# SCH_LEFT_2025-11-04.net
KiCad netlist of a schematic drawn in EasyEDA
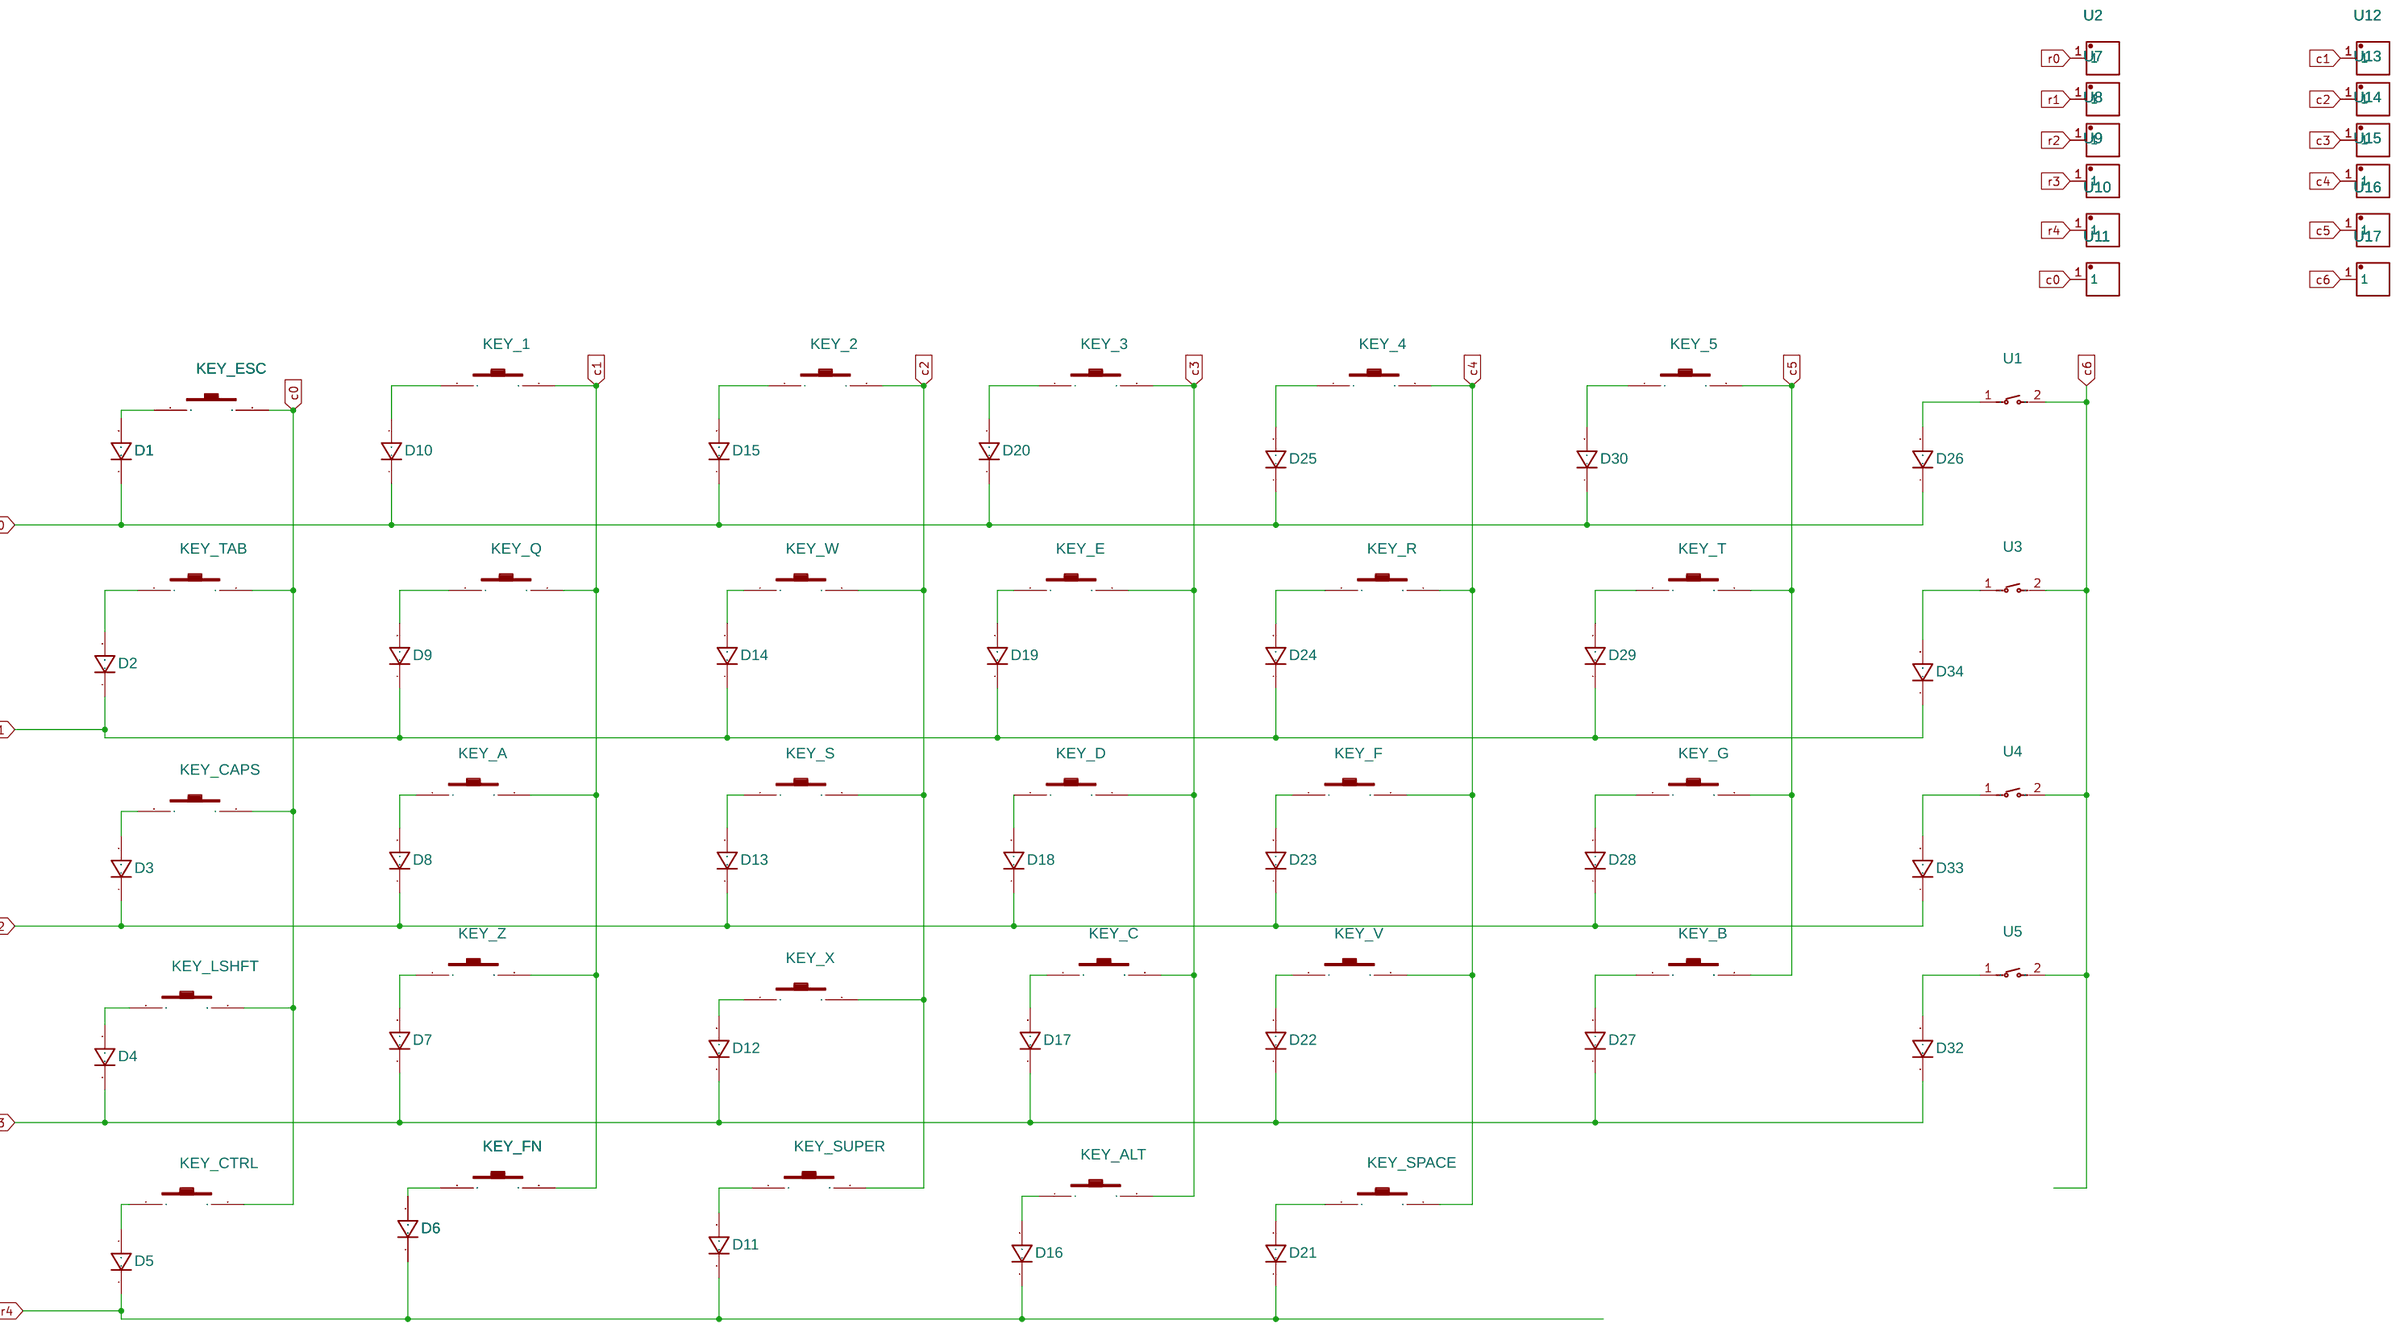
[diagram p0: schematic sheet]

(export (version "E")
  (design (tool "Eeschema 10.0.6"))
  (components
    (comp (ref "D1")
      (value "1N4148W")
      (fields (field (name "Manufacturer") "SMC Diode Solutions"))
      (libsource (lib "") (part "1N4148W"))
    )
    (comp (ref "D2")
      (value "1N4148W")
      (fields (field (name "Manufacturer") "SMC Diode Solutions"))
      (libsource (lib "") (part "1N4148W"))
    )
    (comp (ref "D3")
      (value "1N4148W")
      (fields (field (name "Manufacturer") "SMC Diode Solutions"))
      (libsource (lib "") (part "1N4148W"))
    )
    (comp (ref "D4")
      (value "1N4148W")
      (fields (field (name "Manufacturer") "SMC Diode Solutions"))
      (libsource (lib "") (part "1N4148W"))
    )
    (comp (ref "D5")
      (value "1N4148W")
      (fields (field (name "Manufacturer") "SMC Diode Solutions"))
      (libsource (lib "") (part "1N4148W"))
    )
    (comp (ref "D6")
      (value "1N4148W")
      (fields (field (name "Manufacturer") "SMC Diode Solutions"))
      (libsource (lib "") (part "1N4148W"))
    )
    (comp (ref "D7")
      (value "1N4148W")
      (fields (field (name "Manufacturer") "SMC Diode Solutions"))
      (libsource (lib "") (part "1N4148W"))
    )
    (comp (ref "D8")
      (value "1N4148W")
      (fields (field (name "Manufacturer") "SMC Diode Solutions"))
      (libsource (lib "") (part "1N4148W"))
    )
    (comp (ref "D9")
      (value "1N4148W")
      (fields (field (name "Manufacturer") "SMC Diode Solutions"))
      (libsource (lib "") (part "1N4148W"))
    )
    (comp (ref "D10")
      (value "1N4148W")
      (fields (field (name "Manufacturer") "SMC Diode Solutions"))
      (libsource (lib "") (part "1N4148W"))
    )
    (comp (ref "D11")
      (value "1N4148W")
      (fields (field (name "Manufacturer") "SMC Diode Solutions"))
      (libsource (lib "") (part "1N4148W"))
    )
    (comp (ref "D12")
      (value "1N4148W")
      (fields (field (name "Manufacturer") "SMC Diode Solutions"))
      (libsource (lib "") (part "1N4148W"))
    )
    (comp (ref "D13")
      (value "1N4148W")
      (fields (field (name "Manufacturer") "SMC Diode Solutions"))
      (libsource (lib "") (part "1N4148W"))
    )
    (comp (ref "D14")
      (value "1N4148W")
      (fields (field (name "Manufacturer") "SMC Diode Solutions"))
      (libsource (lib "") (part "1N4148W"))
    )
    (comp (ref "D15")
      (value "1N4148W")
      (fields (field (name "Manufacturer") "SMC Diode Solutions"))
      (libsource (lib "") (part "1N4148W"))
    )
    (comp (ref "D16")
      (value "1N4148W")
      (fields (field (name "Manufacturer") "SMC Diode Solutions"))
      (libsource (lib "") (part "1N4148W"))
    )
    (comp (ref "D17")
      (value "1N4148W")
      (fields (field (name "Manufacturer") "SMC Diode Solutions"))
      (libsource (lib "") (part "1N4148W"))
    )
    (comp (ref "D18")
      (value "1N4148W")
      (fields (field (name "Manufacturer") "SMC Diode Solutions"))
      (libsource (lib "") (part "1N4148W"))
    )
    (comp (ref "D19")
      (value "1N4148W")
      (fields (field (name "Manufacturer") "SMC Diode Solutions"))
      (libsource (lib "") (part "1N4148W"))
    )
    (comp (ref "D20")
      (value "1N4148W")
      (fields (field (name "Manufacturer") "SMC Diode Solutions"))
      (libsource (lib "") (part "1N4148W"))
    )
    (comp (ref "D21")
      (value "1N4148W")
      (fields (field (name "Manufacturer") "SMC Diode Solutions"))
      (libsource (lib "") (part "1N4148W"))
    )
    (comp (ref "D22")
      (value "1N4148W")
      (fields (field (name "Manufacturer") "SMC Diode Solutions"))
      (libsource (lib "") (part "1N4148W"))
    )
    (comp (ref "D23")
      (value "1N4148W")
      (fields (field (name "Manufacturer") "SMC Diode Solutions"))
      (libsource (lib "") (part "1N4148W"))
    )
    (comp (ref "D24")
      (value "1N4148W")
      (fields (field (name "Manufacturer") "SMC Diode Solutions"))
      (libsource (lib "") (part "1N4148W"))
    )
    (comp (ref "D25")
      (value "1N4148W")
      (fields (field (name "Manufacturer") "SMC Diode Solutions"))
      (libsource (lib "") (part "1N4148W"))
    )
    (comp (ref "D26")
      (value "1N4148W")
      (fields (field (name "Manufacturer") "SMC Diode Solutions"))
      (libsource (lib "") (part "1N4148W"))
    )
    (comp (ref "D27")
      (value "1N4148W")
      (fields (field (name "Manufacturer") "SMC Diode Solutions"))
      (libsource (lib "") (part "1N4148W"))
    )
    (comp (ref "D28")
      (value "1N4148W")
      (fields (field (name "Manufacturer") "SMC Diode Solutions"))
      (libsource (lib "") (part "1N4148W"))
    )
    (comp (ref "D29")
      (value "1N4148W")
      (fields (field (name "Manufacturer") "SMC Diode Solutions"))
      (libsource (lib "") (part "1N4148W"))
    )
    (comp (ref "D30")
      (value "1N4148W")
      (fields (field (name "Manufacturer") "SMC Diode Solutions"))
      (libsource (lib "") (part "1N4148W"))
    )
    (comp (ref "D32")
      (value "1N4148W")
      (fields (field (name "Manufacturer") "SMC Diode Solutions"))
      (libsource (lib "") (part "1N4148W"))
    )
    (comp (ref "D33")
      (value "1N4148W")
      (fields (field (name "Manufacturer") "SMC Diode Solutions"))
      (libsource (lib "") (part "1N4148W"))
    )
    (comp (ref "D34")
      (value "1N4148W")
      (fields (field (name "Manufacturer") "SMC Diode Solutions"))
      (libsource (lib "") (part "1N4148W"))
    )
    (comp (ref "KEY_1") (value "Outemu Switch") (libsource (lib "") (part "Outemu Switch_14")))
    (comp (ref "KEY_2") (value "Outemu Switch") (libsource (lib "") (part "Outemu Switch_14")))
    (comp (ref "KEY_3") (value "Outemu Switch") (libsource (lib "") (part "Outemu Switch_14")))
    (comp (ref "KEY_4") (value "Outemu Switch") (libsource (lib "") (part "Outemu Switch_14")))
    (comp (ref "KEY_5") (value "Outemu Switch") (libsource (lib "") (part "Outemu Switch_14")))
    (comp (ref "KEY_A") (value "Outemu Switch") (libsource (lib "") (part "Outemu Switch_1")))
    (comp (ref "KEY_ALT") (value "Outemu Switch") (libsource (lib "") (part "Outemu Switch_13")))
    (comp (ref "KEY_B") (value "Outemu Switch") (libsource (lib "") (part "Outemu Switch_8")))
    (comp (ref "KEY_C") (value "Outemu Switch") (libsource (lib "") (part "Outemu Switch_16")))
    (comp (ref "KEY_CAPS") (value "Outemu Switch") (libsource (lib "") (part "Outemu Switch_10")))
    (comp (ref "KEY_CTRL") (value "Outemu Switch") (libsource (lib "") (part "Outemu Switch_17")))
    (comp (ref "KEY_D") (value "Outemu Switch") (libsource (lib "") (part "Outemu Switch_12")))
    (comp (ref "KEY_E") (value "Outemu Switch") (libsource (lib "") (part "Outemu Switch_3")))
    (comp (ref "KEY_ESC") (value "Outemu Switch") (libsource (lib "") (part "Outemu Switch")))
    (comp (ref "KEY_F") (value "Outemu Switch") (libsource (lib "") (part "Outemu Switch_18")))
    (comp (ref "KEY_FN") (value "Outemu Switch") (libsource (lib "") (part "Outemu Switch_11")))
    (comp (ref "KEY_G") (value "Outemu Switch") (libsource (lib "") (part "Outemu Switch_20")))
    (comp (ref "KEY_LSHFT") (value "Outemu Switch") (libsource (lib "") (part "Outemu Switch_22")))
    (comp (ref "KEY_Q") (value "Outemu Switch") (libsource (lib "") (part "Outemu Switch_2")))
    (comp (ref "KEY_R") (value "Outemu Switch") (libsource (lib "") (part "Outemu Switch_24")))
    (comp (ref "KEY_S") (value "Outemu Switch") (libsource (lib "") (part "Outemu Switch_9")))
    (comp (ref "KEY_SPACE") (value "Outemu Switch") (libsource (lib "") (part "Outemu Switch_19")))
    (comp (ref "KEY_SUPER") (value "Outemu Switch") (libsource (lib "") (part "Outemu Switch_7")))
    (comp (ref "KEY_T") (value "Outemu Switch") (libsource (lib "") (part "Outemu Switch_21")))
    (comp (ref "KEY_TAB") (value "Outemu Switch") (libsource (lib "") (part "Outemu Switch_15")))
    (comp (ref "KEY_V") (value "Outemu Switch") (libsource (lib "") (part "Outemu Switch_6")))
    (comp (ref "KEY_W") (value "Outemu Switch") (libsource (lib "") (part "Outemu Switch_4")))
    (comp (ref "KEY_X") (value "Outemu Switch") (libsource (lib "") (part "Outemu Switch_5")))
    (comp (ref "KEY_Z") (value "Outemu Switch") (libsource (lib "") (part "Outemu Switch_23")))
    (comp (ref "U1")
      (value "ZX-QC34-2TPDZ")
      (fields (field (name "Manufacturer") "Megastar(兆星)"))
      (libsource (lib "") (part "ZX-QC34-2TPDZ"))
    )
    (comp (ref "U2")
      (value "54102-T06-00")
      (fields (field (name "Manufacturer") "Amphenol"))
      (libsource (lib "") (part "54102-T06-00"))
    )
    (comp (ref "U3")
      (value "ZX-QC34-2TPDZ")
      (fields (field (name "Manufacturer") "Megastar(兆星)"))
      (libsource (lib "") (part "ZX-QC34-2TPDZ"))
    )
    (comp (ref "U4")
      (value "ZX-QC34-2TPDZ")
      (fields (field (name "Manufacturer") "Megastar(兆星)"))
      (libsource (lib "") (part "ZX-QC34-2TPDZ"))
    )
    (comp (ref "U5")
      (value "ZX-QC34-2TPDZ")
      (fields (field (name "Manufacturer") "Megastar(兆星)"))
      (libsource (lib "") (part "ZX-QC34-2TPDZ"))
    )
    (comp (ref "U7")
      (value "54102-T06-00")
      (fields (field (name "Manufacturer") "Amphenol"))
      (libsource (lib "") (part "54102-T06-00"))
    )
    (comp (ref "U8")
      (value "54102-T06-00")
      (fields (field (name "Manufacturer") "Amphenol"))
      (libsource (lib "") (part "54102-T06-00"))
    )
    (comp (ref "U9")
      (value "54102-T06-00")
      (fields (field (name "Manufacturer") "Amphenol"))
      (libsource (lib "") (part "54102-T06-00"))
    )
    (comp (ref "U10")
      (value "54102-T06-00")
      (fields (field (name "Manufacturer") "Amphenol"))
      (libsource (lib "") (part "54102-T06-00"))
    )
    (comp (ref "U11")
      (value "54102-T06-00")
      (fields (field (name "Manufacturer") "Amphenol"))
      (libsource (lib "") (part "54102-T06-00"))
    )
    (comp (ref "U12")
      (value "54102-T06-00")
      (fields (field (name "Manufacturer") "Amphenol"))
      (libsource (lib "") (part "54102-T06-00"))
    )
    (comp (ref "U13")
      (value "54102-T06-00")
      (fields (field (name "Manufacturer") "Amphenol"))
      (libsource (lib "") (part "54102-T06-00"))
    )
    (comp (ref "U14")
      (value "54102-T06-00")
      (fields (field (name "Manufacturer") "Amphenol"))
      (libsource (lib "") (part "54102-T06-00"))
    )
    (comp (ref "U15")
      (value "54102-T06-00")
      (fields (field (name "Manufacturer") "Amphenol"))
      (libsource (lib "") (part "54102-T06-00"))
    )
    (comp (ref "U16")
      (value "54102-T06-00")
      (fields (field (name "Manufacturer") "Amphenol"))
      (libsource (lib "") (part "54102-T06-00"))
    )
    (comp (ref "U17")
      (value "54102-T06-00")
      (fields (field (name "Manufacturer") "Amphenol"))
      (libsource (lib "") (part "54102-T06-00"))
    )
  )
  (nets
    (net (code "1") (name "Net-(D1-Pad2)") (class "Default")
      (node (ref "D1") (pin "2") (pinfunction "2_2") (pintype "unspecified"))
      (node (ref "KEY_ESC") (pin "1") (pinfunction "1_1") (pintype "input"))
    )
    (net (code "2") (name "Net-(D2-Pad2)") (class "Default")
      (node (ref "D2") (pin "2") (pinfunction "2_2") (pintype "unspecified"))
      (node (ref "KEY_TAB") (pin "1") (pinfunction "1_1") (pintype "input"))
    )
    (net (code "3") (name "Net-(D3-Pad2)") (class "Default")
      (node (ref "D3") (pin "2") (pinfunction "2_2") (pintype "unspecified"))
      (node (ref "KEY_CAPS") (pin "1") (pinfunction "1_1") (pintype "input"))
    )
    (net (code "4") (name "Net-(D4-Pad2)") (class "Default")
      (node (ref "D4") (pin "2") (pinfunction "2_2") (pintype "unspecified"))
      (node (ref "KEY_LSHFT") (pin "1") (pinfunction "1_1") (pintype "input"))
    )
    (net (code "5") (name "Net-(D5-Pad2)") (class "Default")
      (node (ref "D5") (pin "2") (pinfunction "2_2") (pintype "unspecified"))
      (node (ref "KEY_CTRL") (pin "1") (pinfunction "1_1") (pintype "input"))
    )
    (net (code "6") (name "Net-(D6-Pad2)") (class "Default")
      (node (ref "D6") (pin "2") (pinfunction "2_2") (pintype "unspecified"))
      (node (ref "KEY_FN") (pin "1") (pinfunction "1_1") (pintype "input"))
    )
    (net (code "7") (name "Net-(D7-Pad2)") (class "Default")
      (node (ref "D7") (pin "2") (pinfunction "2_2") (pintype "unspecified"))
      (node (ref "KEY_Z") (pin "1") (pinfunction "1_1") (pintype "input"))
    )
    (net (code "8") (name "Net-(D8-Pad2)") (class "Default")
      (node (ref "D8") (pin "2") (pinfunction "2_2") (pintype "unspecified"))
      (node (ref "KEY_A") (pin "1") (pinfunction "1_1") (pintype "input"))
    )
    (net (code "9") (name "Net-(D9-Pad2)") (class "Default")
      (node (ref "D9") (pin "2") (pinfunction "2_2") (pintype "unspecified"))
      (node (ref "KEY_Q") (pin "1") (pinfunction "1_1") (pintype "input"))
    )
    (net (code "10") (name "Net-(D10-Pad2)") (class "Default")
      (node (ref "D10") (pin "2") (pinfunction "2_2") (pintype "unspecified"))
      (node (ref "KEY_1") (pin "1") (pinfunction "1_1") (pintype "input"))
    )
    (net (code "11") (name "Net-(D11-Pad2)") (class "Default")
      (node (ref "D11") (pin "2") (pinfunction "2_2") (pintype "unspecified"))
      (node (ref "KEY_SUPER") (pin "1") (pinfunction "1_1") (pintype "input"))
    )
    (net (code "12") (name "Net-(D12-Pad2)") (class "Default")
      (node (ref "D12") (pin "2") (pinfunction "2_2") (pintype "unspecified"))
      (node (ref "KEY_X") (pin "1") (pinfunction "1_1") (pintype "input"))
    )
    (net (code "13") (name "Net-(D13-Pad2)") (class "Default")
      (node (ref "D13") (pin "2") (pinfunction "2_2") (pintype "unspecified"))
      (node (ref "KEY_S") (pin "1") (pinfunction "1_1") (pintype "input"))
    )
    (net (code "14") (name "Net-(D14-Pad2)") (class "Default")
      (node (ref "D14") (pin "2") (pinfunction "2_2") (pintype "unspecified"))
      (node (ref "KEY_W") (pin "1") (pinfunction "1_1") (pintype "input"))
    )
    (net (code "15") (name "Net-(D15-Pad2)") (class "Default")
      (node (ref "D15") (pin "2") (pinfunction "2_2") (pintype "unspecified"))
      (node (ref "KEY_2") (pin "1") (pinfunction "1_1") (pintype "input"))
    )
    (net (code "16") (name "Net-(D16-Pad2)") (class "Default")
      (node (ref "D16") (pin "2") (pinfunction "2_2") (pintype "unspecified"))
      (node (ref "KEY_ALT") (pin "1") (pinfunction "1_1") (pintype "input"))
    )
    (net (code "17") (name "Net-(D17-Pad2)") (class "Default")
      (node (ref "D17") (pin "2") (pinfunction "2_2") (pintype "unspecified"))
      (node (ref "KEY_C") (pin "1") (pinfunction "1_1") (pintype "input"))
    )
    (net (code "18") (name "Net-(D18-Pad2)") (class "Default")
      (node (ref "D18") (pin "2") (pinfunction "2_2") (pintype "unspecified"))
      (node (ref "KEY_D") (pin "1") (pinfunction "1_1") (pintype "input"))
    )
    (net (code "19") (name "Net-(D19-Pad2)") (class "Default")
      (node (ref "D19") (pin "2") (pinfunction "2_2") (pintype "unspecified"))
      (node (ref "KEY_E") (pin "1") (pinfunction "1_1") (pintype "input"))
    )
    (net (code "20") (name "Net-(D20-Pad2)") (class "Default")
      (node (ref "D20") (pin "2") (pinfunction "2_2") (pintype "unspecified"))
      (node (ref "KEY_3") (pin "1") (pinfunction "1_1") (pintype "input"))
    )
    (net (code "21") (name "Net-(D21-Pad2)") (class "Default")
      (node (ref "D21") (pin "2") (pinfunction "2_2") (pintype "unspecified"))
      (node (ref "KEY_SPACE") (pin "1") (pinfunction "1_1") (pintype "input"))
    )
    (net (code "22") (name "Net-(D22-Pad2)") (class "Default")
      (node (ref "D22") (pin "2") (pinfunction "2_2") (pintype "unspecified"))
      (node (ref "KEY_V") (pin "1") (pinfunction "1_1") (pintype "input"))
    )
    (net (code "23") (name "Net-(D23-Pad2)") (class "Default")
      (node (ref "D23") (pin "2") (pinfunction "2_2") (pintype "unspecified"))
      (node (ref "KEY_F") (pin "1") (pinfunction "1_1") (pintype "input"))
    )
    (net (code "24") (name "Net-(D24-Pad2)") (class "Default")
      (node (ref "D24") (pin "2") (pinfunction "2_2") (pintype "unspecified"))
      (node (ref "KEY_R") (pin "1") (pinfunction "1_1") (pintype "input"))
    )
    (net (code "25") (name "Net-(D25-Pad2)") (class "Default")
      (node (ref "D25") (pin "2") (pinfunction "2_2") (pintype "unspecified"))
      (node (ref "KEY_4") (pin "1") (pinfunction "1_1") (pintype "input"))
    )
    (net (code "26") (name "Net-(D26-Pad2)") (class "Default")
      (node (ref "D26") (pin "2") (pinfunction "2_2") (pintype "unspecified"))
      (node (ref "U1") (pin "1") (pinfunction "1_1") (pintype "unspecified"))
    )
    (net (code "27") (name "Net-(D27-Pad2)") (class "Default")
      (node (ref "D27") (pin "2") (pinfunction "2_2") (pintype "unspecified"))
      (node (ref "KEY_B") (pin "1") (pinfunction "1_1") (pintype "input"))
    )
    (net (code "28") (name "Net-(D28-Pad2)") (class "Default")
      (node (ref "D28") (pin "2") (pinfunction "2_2") (pintype "unspecified"))
      (node (ref "KEY_G") (pin "1") (pinfunction "1_1") (pintype "input"))
    )
    (net (code "29") (name "Net-(D29-Pad2)") (class "Default")
      (node (ref "D29") (pin "2") (pinfunction "2_2") (pintype "unspecified"))
      (node (ref "KEY_T") (pin "1") (pinfunction "1_1") (pintype "input"))
    )
    (net (code "30") (name "Net-(D30-Pad2)") (class "Default")
      (node (ref "D30") (pin "2") (pinfunction "2_2") (pintype "unspecified"))
      (node (ref "KEY_5") (pin "1") (pinfunction "1_1") (pintype "input"))
    )
    (net (code "31") (name "Net-(D32-Pad2)") (class "Default")
      (node (ref "D32") (pin "2") (pinfunction "2_2") (pintype "unspecified"))
      (node (ref "U5") (pin "1") (pinfunction "1_1") (pintype "unspecified"))
    )
    (net (code "32") (name "Net-(D33-Pad2)") (class "Default")
      (node (ref "D33") (pin "2") (pinfunction "2_2") (pintype "unspecified"))
      (node (ref "U4") (pin "1") (pinfunction "1_1") (pintype "unspecified"))
    )
    (net (code "33") (name "Net-(D34-Pad2)") (class "Default")
      (node (ref "D34") (pin "2") (pinfunction "2_2") (pintype "unspecified"))
      (node (ref "U3") (pin "1") (pinfunction "1_1") (pintype "unspecified"))
    )
    (net (code "34") (name "c0") (class "Default")
      (node (ref "KEY_CAPS") (pin "2") (pinfunction "2_2") (pintype "input"))
      (node (ref "KEY_CTRL") (pin "2") (pinfunction "2_2") (pintype "input"))
      (node (ref "KEY_ESC") (pin "2") (pinfunction "2_2") (pintype "input"))
      (node (ref "KEY_LSHFT") (pin "2") (pinfunction "2_2") (pintype "input"))
      (node (ref "KEY_TAB") (pin "2") (pinfunction "2_2") (pintype "input"))
      (node (ref "U11") (pin "1") (pinfunction "1_1") (pintype "unspecified"))
    )
    (net (code "35") (name "c1") (class "Default")
      (node (ref "KEY_1") (pin "2") (pinfunction "2_2") (pintype "input"))
      (node (ref "KEY_A") (pin "2") (pinfunction "2_2") (pintype "input"))
      (node (ref "KEY_FN") (pin "2") (pinfunction "2_2") (pintype "input"))
      (node (ref "KEY_Q") (pin "2") (pinfunction "2_2") (pintype "input"))
      (node (ref "KEY_Z") (pin "2") (pinfunction "2_2") (pintype "input"))
      (node (ref "U12") (pin "1") (pinfunction "1_1") (pintype "unspecified"))
    )
    (net (code "36") (name "c2") (class "Default")
      (node (ref "KEY_2") (pin "2") (pinfunction "2_2") (pintype "input"))
      (node (ref "KEY_S") (pin "2") (pinfunction "2_2") (pintype "input"))
      (node (ref "KEY_SUPER") (pin "2") (pinfunction "2_2") (pintype "input"))
      (node (ref "KEY_W") (pin "2") (pinfunction "2_2") (pintype "input"))
      (node (ref "KEY_X") (pin "2") (pinfunction "2_2") (pintype "input"))
      (node (ref "U13") (pin "1") (pinfunction "1_1") (pintype "unspecified"))
    )
    (net (code "37") (name "c3") (class "Default")
      (node (ref "KEY_3") (pin "2") (pinfunction "2_2") (pintype "input"))
      (node (ref "KEY_ALT") (pin "2") (pinfunction "2_2") (pintype "input"))
      (node (ref "KEY_C") (pin "2") (pinfunction "2_2") (pintype "input"))
      (node (ref "KEY_D") (pin "2") (pinfunction "2_2") (pintype "input"))
      (node (ref "KEY_E") (pin "2") (pinfunction "2_2") (pintype "input"))
      (node (ref "U14") (pin "1") (pinfunction "1_1") (pintype "unspecified"))
    )
    (net (code "38") (name "c4") (class "Default")
      (node (ref "KEY_4") (pin "2") (pinfunction "2_2") (pintype "input"))
      (node (ref "KEY_F") (pin "2") (pinfunction "2_2") (pintype "input"))
      (node (ref "KEY_R") (pin "2") (pinfunction "2_2") (pintype "input"))
      (node (ref "KEY_SPACE") (pin "2") (pinfunction "2_2") (pintype "input"))
      (node (ref "KEY_V") (pin "2") (pinfunction "2_2") (pintype "input"))
      (node (ref "U15") (pin "1") (pinfunction "1_1") (pintype "unspecified"))
    )
    (net (code "39") (name "c5") (class "Default")
      (node (ref "KEY_5") (pin "2") (pinfunction "2_2") (pintype "input"))
      (node (ref "KEY_B") (pin "2") (pinfunction "2_2") (pintype "input"))
      (node (ref "KEY_G") (pin "2") (pinfunction "2_2") (pintype "input"))
      (node (ref "KEY_T") (pin "2") (pinfunction "2_2") (pintype "input"))
      (node (ref "U16") (pin "1") (pinfunction "1_1") (pintype "unspecified"))
    )
    (net (code "40") (name "c6") (class "Default")
      (node (ref "U1") (pin "2") (pinfunction "2_2") (pintype "unspecified"))
      (node (ref "U17") (pin "1") (pinfunction "1_1") (pintype "unspecified"))
      (node (ref "U3") (pin "2") (pinfunction "2_2") (pintype "unspecified"))
      (node (ref "U4") (pin "2") (pinfunction "2_2") (pintype "unspecified"))
      (node (ref "U5") (pin "2") (pinfunction "2_2") (pintype "unspecified"))
    )
    (net (code "41") (name "r0") (class "Default")
      (node (ref "D1") (pin "1") (pinfunction "1_1") (pintype "unspecified"))
      (node (ref "D10") (pin "1") (pinfunction "1_1") (pintype "unspecified"))
      (node (ref "D15") (pin "1") (pinfunction "1_1") (pintype "unspecified"))
      (node (ref "D20") (pin "1") (pinfunction "1_1") (pintype "unspecified"))
      (node (ref "D25") (pin "1") (pinfunction "1_1") (pintype "unspecified"))
      (node (ref "D26") (pin "1") (pinfunction "1_1") (pintype "unspecified"))
      (node (ref "D30") (pin "1") (pinfunction "1_1") (pintype "unspecified"))
      (node (ref "U2") (pin "1") (pinfunction "1_1") (pintype "unspecified"))
    )
    (net (code "42") (name "r1") (class "Default")
      (node (ref "D14") (pin "1") (pinfunction "1_1") (pintype "unspecified"))
      (node (ref "D19") (pin "1") (pinfunction "1_1") (pintype "unspecified"))
      (node (ref "D2") (pin "1") (pinfunction "1_1") (pintype "unspecified"))
      (node (ref "D24") (pin "1") (pinfunction "1_1") (pintype "unspecified"))
      (node (ref "D29") (pin "1") (pinfunction "1_1") (pintype "unspecified"))
      (node (ref "D34") (pin "1") (pinfunction "1_1") (pintype "unspecified"))
      (node (ref "D9") (pin "1") (pinfunction "1_1") (pintype "unspecified"))
      (node (ref "U7") (pin "1") (pinfunction "1_1") (pintype "unspecified"))
    )
    (net (code "43") (name "r2") (class "Default")
      (node (ref "D13") (pin "1") (pinfunction "1_1") (pintype "unspecified"))
      (node (ref "D18") (pin "1") (pinfunction "1_1") (pintype "unspecified"))
      (node (ref "D23") (pin "1") (pinfunction "1_1") (pintype "unspecified"))
      (node (ref "D28") (pin "1") (pinfunction "1_1") (pintype "unspecified"))
      (node (ref "D3") (pin "1") (pinfunction "1_1") (pintype "unspecified"))
      (node (ref "D33") (pin "1") (pinfunction "1_1") (pintype "unspecified"))
      (node (ref "D8") (pin "1") (pinfunction "1_1") (pintype "unspecified"))
      (node (ref "U8") (pin "1") (pinfunction "1_1") (pintype "unspecified"))
    )
    (net (code "44") (name "r3") (class "Default")
      (node (ref "D12") (pin "1") (pinfunction "1_1") (pintype "unspecified"))
      (node (ref "D17") (pin "1") (pinfunction "1_1") (pintype "unspecified"))
      (node (ref "D22") (pin "1") (pinfunction "1_1") (pintype "unspecified"))
      (node (ref "D27") (pin "1") (pinfunction "1_1") (pintype "unspecified"))
      (node (ref "D32") (pin "1") (pinfunction "1_1") (pintype "unspecified"))
      (node (ref "D4") (pin "1") (pinfunction "1_1") (pintype "unspecified"))
      (node (ref "D7") (pin "1") (pinfunction "1_1") (pintype "unspecified"))
      (node (ref "U9") (pin "1") (pinfunction "1_1") (pintype "unspecified"))
    )
    (net (code "45") (name "r4") (class "Default")
      (node (ref "D11") (pin "1") (pinfunction "1_1") (pintype "unspecified"))
      (node (ref "D16") (pin "1") (pinfunction "1_1") (pintype "unspecified"))
      (node (ref "D21") (pin "1") (pinfunction "1_1") (pintype "unspecified"))
      (node (ref "D5") (pin "1") (pinfunction "1_1") (pintype "unspecified"))
      (node (ref "D6") (pin "1") (pinfunction "1_1") (pintype "unspecified"))
      (node (ref "U10") (pin "1") (pinfunction "1_1") (pintype "unspecified"))
    )
  )
)
